# chuveiro.net
KiCad netlist of a schematic drawn in EAGLE
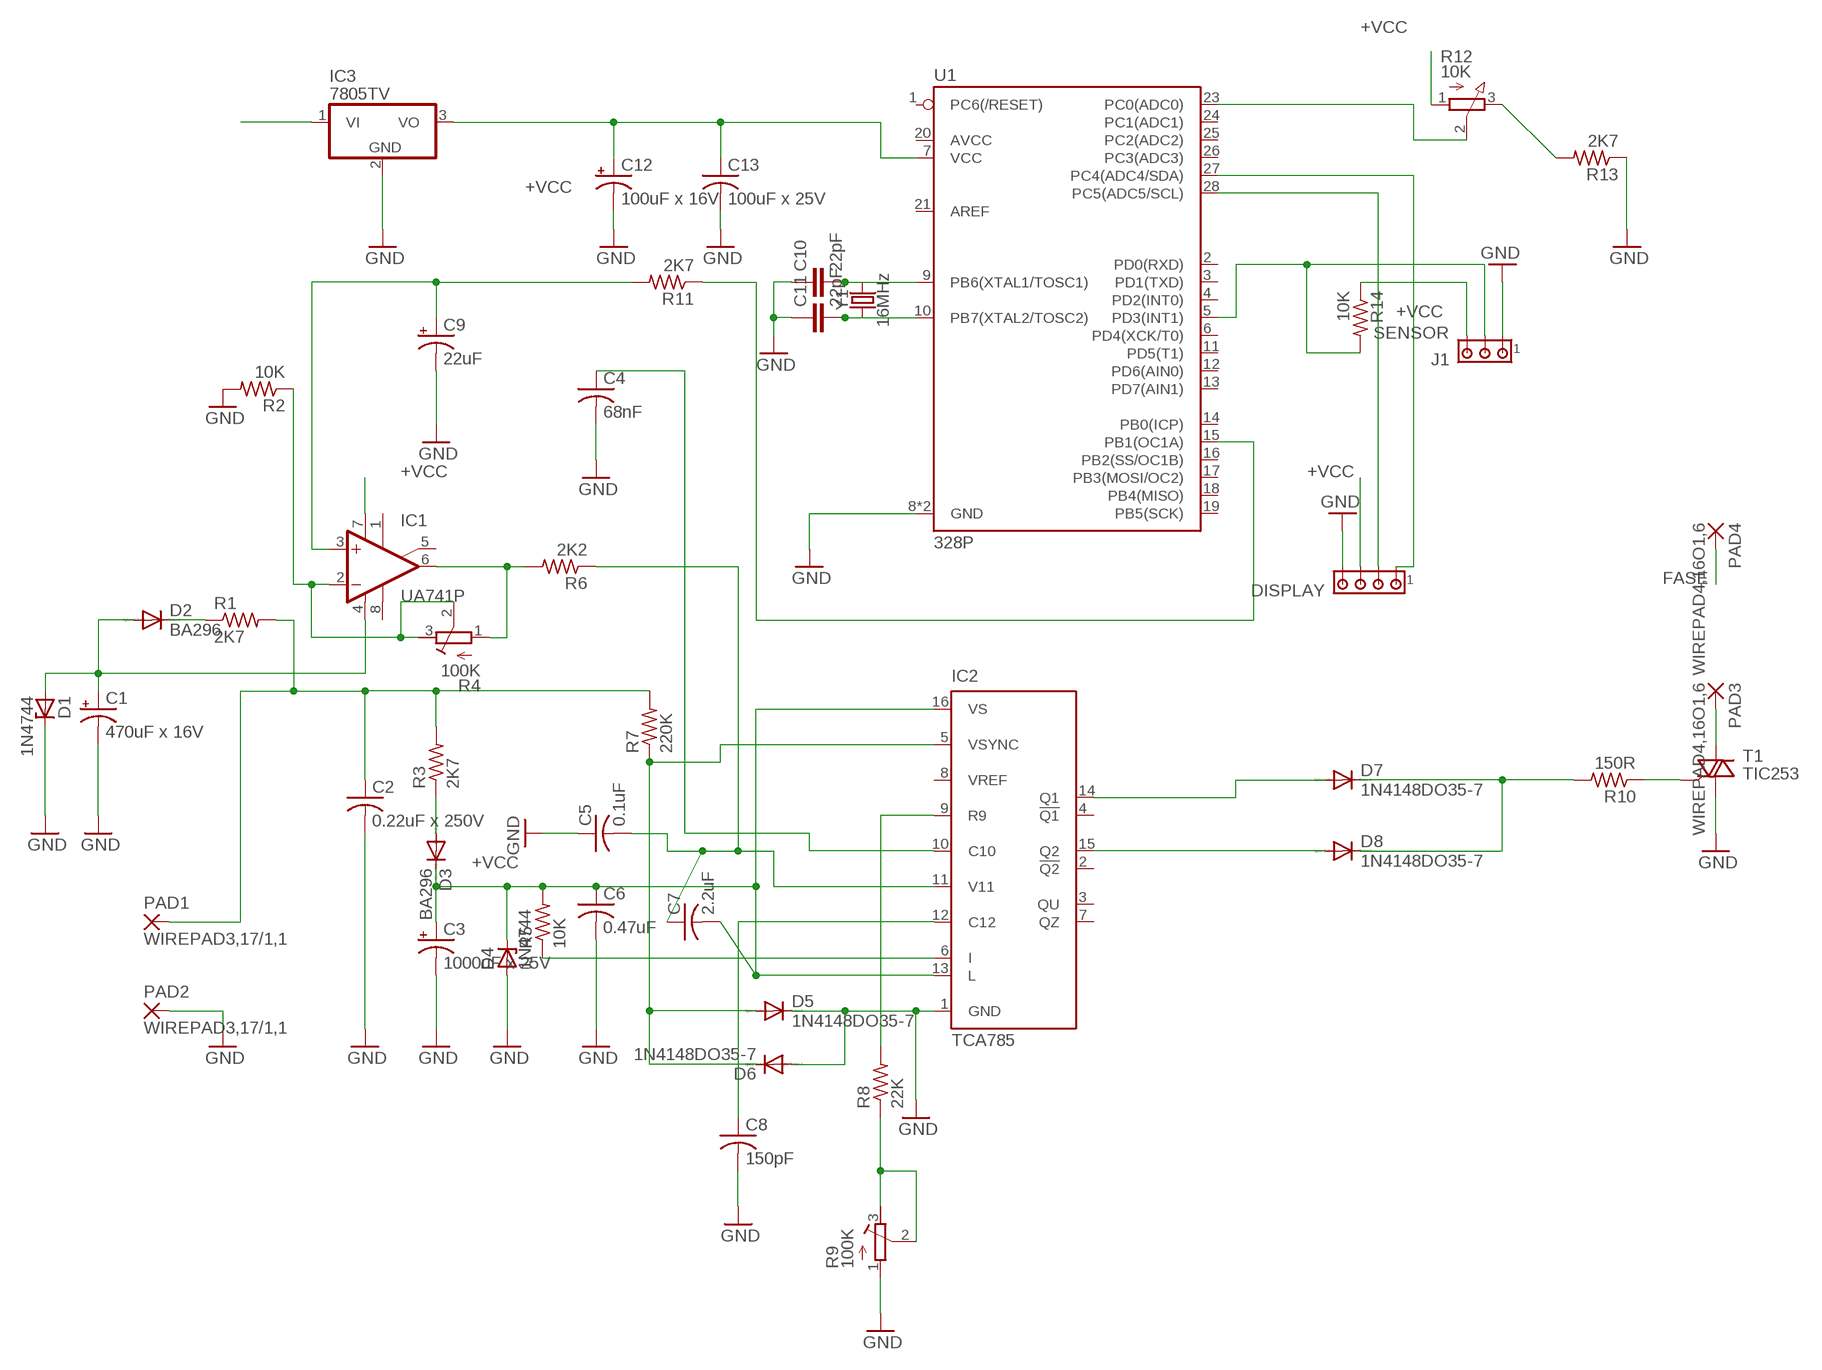
[diagram p0: schematic, sheet 1]

(export (version "E")
  (design (tool "Eeschema 10.0.6"))
  (components
    (comp (ref "C1")
      (value "470uF x 16V")
      (footprint "eagle-import:E5-6")
      (libsource (lib "eagle-import") (part "CPOL-USE5-6"))
    )
    (comp (ref "C2")
      (value "0.22uF x 250V")
      (footprint "eagle-import:C225-062X268")
      (libsource (lib "eagle-import") (part "C-US225-062X268"))
    )
    (comp (ref "C3")
      (value "1000uF x 25V")
      (footprint "eagle-import:E5-6")
      (libsource (lib "eagle-import") (part "CPOL-USE5-6"))
    )
    (comp (ref "C4")
      (value "68nF")
      (footprint "eagle-import:C025-050X050")
      (libsource (lib "eagle-import") (part "C-US025-050X050"))
    )
    (comp (ref "C5")
      (value "0.1uF")
      (footprint "eagle-import:C025-050X050")
      (libsource (lib "eagle-import") (part "C-US025-050X050"))
    )
    (comp (ref "C6")
      (value "0.47uF")
      (footprint "eagle-import:C025-050X050")
      (libsource (lib "eagle-import") (part "C-US025-050X050"))
    )
    (comp (ref "C7")
      (value "2.2uF")
      (footprint "eagle-import:C025-050X050")
      (libsource (lib "eagle-import") (part "C-US025-050X050"))
    )
    (comp (ref "C8")
      (value "150pF")
      (footprint "eagle-import:C025-050X050")
      (libsource (lib "eagle-import") (part "C-US025-050X050"))
    )
    (comp (ref "C9")
      (value "22uF")
      (footprint "eagle-import:E5-6")
      (libsource (lib "eagle-import") (part "CPOL-USE5-6"))
    )
    (comp (ref "C10")
      (value "22pF")
      (footprint "eagle-import:C025-024X044")
      (libsource (lib "eagle-import") (part "C-EU025-024X044"))
    )
    (comp (ref "C11")
      (value "22pF")
      (footprint "eagle-import:C025-024X044")
      (libsource (lib "eagle-import") (part "C-EU025-024X044"))
    )
    (comp (ref "C12")
      (value "100uF x 16V")
      (footprint "eagle-import:E5-6")
      (libsource (lib "eagle-import") (part "CPOL-USE5-6"))
    )
    (comp (ref "C13")
      (value "100uF x 25V")
      (footprint "eagle-import:C225-062X268")
      (libsource (lib "eagle-import") (part "C-US225-062X268"))
    )
    (comp (ref "D1")
      (value "1N4744")
      (footprint "eagle-import:DO41Z10")
      (libsource (lib "eagle-import") (part "ZENER-DIODEDO41Z10"))
    )
    (comp (ref "D2")
      (value "BA296")
      (footprint "eagle-import:P2-15")
      (libsource (lib "eagle-import") (part "BA296"))
    )
    (comp (ref "D3")
      (value "BA296")
      (footprint "eagle-import:P2-15")
      (libsource (lib "eagle-import") (part "BA296"))
    )
    (comp (ref "D4")
      (value "1N4744")
      (footprint "eagle-import:DO41Z10")
      (libsource (lib "eagle-import") (part "ZENER-DIODEDO41Z10"))
    )
    (comp (ref "D5")
      (value "1N4148DO35-7")
      (footprint "eagle-import:DO35-7")
      (libsource (lib "eagle-import") (part "1N4148DO35-7"))
    )
    (comp (ref "D6")
      (value "1N4148DO35-7")
      (footprint "eagle-import:DO35-7")
      (libsource (lib "eagle-import") (part "1N4148DO35-7"))
    )
    (comp (ref "D7")
      (value "1N4148DO35-7")
      (footprint "eagle-import:DO35-7")
      (libsource (lib "eagle-import") (part "1N4148DO35-7"))
    )
    (comp (ref "D8")
      (value "1N4148DO35-7")
      (footprint "eagle-import:DO35-7")
      (libsource (lib "eagle-import") (part "1N4148DO35-7"))
    )
    (comp (ref "DISPLAY")
      (value "MTA04-100")
      (footprint "eagle-import:10X04MTA")
      (libsource (lib "eagle-import") (part "MTA04-100"))
    )
    (comp (ref "IC1")
      (value "UA741P")
      (footprint "eagle-import:DIL08")
      (libsource (lib "eagle-import") (part "741PUA"))
    )
    (comp (ref "IC2")
      (value "TCA785")
      (footprint "eagle-import:DIL16")
      (libsource (lib "eagle-import") (part "TCA785"))
    )
    (comp (ref "IC3")
      (value "7805TV")
      (footprint "eagle-import:TO220V")
      (libsource (lib "eagle-import") (part "78TV05"))
    )
    (comp (ref "J1")
      (value "SENSOR")
      (footprint "eagle-import:10X03MTA")
      (libsource (lib "eagle-import") (part "MTA03-100"))
    )
    (comp (ref "PAD1")
      (value "WIREPAD3,17/1,1")
      (footprint "eagle-import:3,17_1,1")
      (libsource (lib "eagle-import") (part "WIREPAD3,17/1,1"))
    )
    (comp (ref "PAD2")
      (value "WIREPAD3,17/1,1")
      (footprint "eagle-import:3,17_1,1")
      (libsource (lib "eagle-import") (part "WIREPAD3,17/1,1"))
    )
    (comp (ref "PAD3")
      (value "WIREPAD4,16O1,6")
      (footprint "eagle-import:4,16O1,6")
      (libsource (lib "eagle-import") (part "WIREPAD4,16O1,6"))
    )
    (comp (ref "PAD4")
      (value "WIREPAD4,16O1,6")
      (footprint "eagle-import:4,16O1,6")
      (libsource (lib "eagle-import") (part "WIREPAD4,16O1,6"))
    )
    (comp (ref "R1")
      (value "2K7")
      (footprint "eagle-import:0207_10")
      (libsource (lib "eagle-import") (part "R-US_0207/10"))
    )
    (comp (ref "R2")
      (value "10K")
      (footprint "eagle-import:0207_10")
      (libsource (lib "eagle-import") (part "R-US_0207/10"))
    )
    (comp (ref "R3")
      (value "2K7")
      (footprint "eagle-import:0207_10")
      (libsource (lib "eagle-import") (part "R-US_0207/10"))
    )
    (comp (ref "R4")
      (value "100K")
      (footprint "eagle-import:RTRIM64Y")
      (libsource (lib "eagle-import") (part "R-TRIMM64Y"))
    )
    (comp (ref "R5")
      (value "10K")
      (footprint "eagle-import:0207_10")
      (libsource (lib "eagle-import") (part "R-US_0207/10"))
    )
    (comp (ref "R6")
      (value "2K2")
      (footprint "eagle-import:0207_10")
      (libsource (lib "eagle-import") (part "R-US_0207/10"))
    )
    (comp (ref "R7")
      (value "220K")
      (footprint "eagle-import:0207_10")
      (libsource (lib "eagle-import") (part "R-US_0207/10"))
    )
    (comp (ref "R8")
      (value "22K")
      (footprint "eagle-import:0207_10")
      (libsource (lib "eagle-import") (part "R-US_0207/10"))
    )
    (comp (ref "R9")
      (value "100K")
      (footprint "eagle-import:RTRIM64Y")
      (libsource (lib "eagle-import") (part "R-TRIMM64Y"))
    )
    (comp (ref "R10")
      (value "150R")
      (footprint "eagle-import:0207_10")
      (libsource (lib "eagle-import") (part "resistor_R-US_0207/10"))
    )
    (comp (ref "R11")
      (value "2K7")
      (footprint "eagle-import:0207_10")
      (libsource (lib "eagle-import") (part "R-US_0207/10"))
    )
    (comp (ref "R12")
      (value "10K")
      (footprint "eagle-import:3RP_1610N")
      (libsource (lib "eagle-import") (part "3RP/1610N"))
    )
    (comp (ref "R13")
      (value "2K7")
      (footprint "eagle-import:0207_10")
      (libsource (lib "eagle-import") (part "R-US_0207/10"))
    )
    (comp (ref "R14")
      (value "10K")
      (footprint "eagle-import:0207_10")
      (libsource (lib "eagle-import") (part "R-US_0207/10"))
    )
    (comp (ref "T1")
      (value "TIC253")
      (footprint "eagle-import:TO218DS")
      (libsource (lib "eagle-import") (part "TIC253"))
    )
    (comp (ref "U1")
      (value "328P")
      (footprint "eagle-import:DIP28")
      (libsource (lib "eagle-import") (part "ATMEGA328P_PDIP"))
    )
    (comp (ref "Y1")
      (value "16MHz")
      (footprint "eagle-import:HC49US")
      (libsource (lib "eagle-import") (part "CRYSTAL-16MHZPTH-HC49US"))
    )
  )
  (nets
    (net (code "1") (name "/+VCC") (class "Default")
      (node (ref "C3") (pin "+") (pinfunction "+_+") (pintype "passive"))
      (node (ref "C6") (pin "1") (pinfunction "1_1") (pintype "passive"))
      (node (ref "C7") (pin "2") (pinfunction "2_2") (pintype "passive"))
      (node (ref "D3") (pin "C") (pinfunction "C_C") (pintype "passive"))
      (node (ref "D4") (pin "C") (pinfunction "C_C") (pintype "passive"))
      (node (ref "DISPLAY") (pin "3") (pinfunction "3_3") (pintype "passive"))
      (node (ref "IC1") (pin "7") (pinfunction "V+_7") (pintype "power_in"))
      (node (ref "IC2") (pin "13") (pinfunction "L_13") (pintype "input"))
      (node (ref "IC2") (pin "16") (pinfunction "VS_16") (pintype "input"))
      (node (ref "IC3") (pin "1") (pinfunction "VI_1") (pintype "input"))
      (node (ref "J1") (pin "3") (pinfunction "3_3") (pintype "passive"))
      (node (ref "R12") (pin "1") (pinfunction "A_1") (pintype "passive"))
      (node (ref "R14") (pin "1") (pinfunction "1_1") (pintype "passive"))
      (node (ref "R5") (pin "2") (pinfunction "2_2") (pintype "passive"))
    )
    (net (code "2") (name "/FASE") (class "Default")
      (node (ref "C2") (pin "1") (pinfunction "1_1") (pintype "passive"))
      (node (ref "PAD1") (pin "1") (pinfunction "P_1") (pintype "passive"))
      (node (ref "PAD4") (pin "1") (pinfunction "P_1") (pintype "passive"))
      (node (ref "R1") (pin "2") (pinfunction "2_2") (pintype "passive"))
      (node (ref "R3") (pin "2") (pinfunction "2_2") (pintype "passive"))
      (node (ref "R7") (pin "2") (pinfunction "2_2") (pintype "passive"))
    )
    (net (code "3") (name "GND") (class "Default")
      (node (ref "C1") (pin "-") (pinfunction "-_-") (pintype "passive"))
      (node (ref "C10") (pin "1") (pinfunction "1_1") (pintype "passive"))
      (node (ref "C11") (pin "1") (pinfunction "1_1") (pintype "passive"))
      (node (ref "C12") (pin "-") (pinfunction "-_-") (pintype "passive"))
      (node (ref "C13") (pin "2") (pinfunction "2_2") (pintype "passive"))
      (node (ref "C2") (pin "2") (pinfunction "2_2") (pintype "passive"))
      (node (ref "C3") (pin "-") (pinfunction "-_-") (pintype "passive"))
      (node (ref "C4") (pin "2") (pinfunction "2_2") (pintype "passive"))
      (node (ref "C5") (pin "1") (pinfunction "1_1") (pintype "passive"))
      (node (ref "C6") (pin "2") (pinfunction "2_2") (pintype "passive"))
      (node (ref "C8") (pin "2") (pinfunction "2_2") (pintype "passive"))
      (node (ref "C9") (pin "-") (pinfunction "-_-") (pintype "passive"))
      (node (ref "D1") (pin "C") (pinfunction "C_C") (pintype "passive"))
      (node (ref "D4") (pin "A") (pinfunction "A_A") (pintype "passive"))
      (node (ref "D5") (pin "C") (pinfunction "C_C") (pintype "passive"))
      (node (ref "D6") (pin "A") (pinfunction "A_A") (pintype "passive"))
      (node (ref "DISPLAY") (pin "4") (pinfunction "4_4") (pintype "passive"))
      (node (ref "IC2") (pin "1") (pinfunction "GND_1") (pintype "power_in"))
      (node (ref "IC3") (pin "2") (pinfunction "GND_2") (pintype "passive"))
      (node (ref "J1") (pin "1") (pinfunction "1_1") (pintype "passive"))
      (node (ref "PAD2") (pin "1") (pinfunction "P_1") (pintype "passive"))
      (node (ref "R13") (pin "1") (pinfunction "1_1") (pintype "passive"))
      (node (ref "R2") (pin "2") (pinfunction "2_2") (pintype "passive"))
      (node (ref "R9") (pin "1") (pinfunction "A_1") (pintype "passive"))
      (node (ref "T1") (pin "A1") (pinfunction "A1_A1") (pintype "passive"))
      (node (ref "U1") (pin "22") (pinfunction "GND_22") (pintype "bidirectional"))
      (node (ref "U1") (pin "8") (pinfunction "GND_8") (pintype "bidirectional"))
    )
    (net (code "4") (name "Net-(D2-PadC)") (class "Default")
      (node (ref "D2") (pin "C") (pinfunction "C_C") (pintype "passive"))
      (node (ref "R1") (pin "1") (pinfunction "1_1") (pintype "passive"))
    )
    (net (code "5") (name "Net-(D3-PadA)") (class "Default")
      (node (ref "D3") (pin "A") (pinfunction "A_A") (pintype "passive"))
      (node (ref "R3") (pin "1") (pinfunction "1_1") (pintype "passive"))
    )
    (net (code "6") (name "Net-(D7-PadC)") (class "Default")
      (node (ref "D7") (pin "C") (pinfunction "C_C") (pintype "passive"))
      (node (ref "D8") (pin "C") (pinfunction "C_C") (pintype "passive"))
      (node (ref "R10") (pin "2") (pinfunction "2_2") (pintype "passive"))
    )
    (net (code "7") (name "Net-(IC1-+IN)") (class "Default")
      (node (ref "C9") (pin "+") (pinfunction "+_+") (pintype "passive"))
      (node (ref "IC1") (pin "3") (pinfunction "+IN_3") (pintype "input"))
      (node (ref "R11") (pin "2") (pinfunction "2_2") (pintype "passive"))
    )
    (net (code "8") (name "Net-(IC1--IN)") (class "Default")
      (node (ref "IC1") (pin "2") (pinfunction "-IN_2") (pintype "input"))
      (node (ref "R2") (pin "1") (pinfunction "1_1") (pintype "passive"))
      (node (ref "R4") (pin "2") (pinfunction "S_2") (pintype "passive"))
      (node (ref "R4") (pin "3") (pinfunction "E_3") (pintype "passive"))
    )
    (net (code "9") (name "Net-(IC1-OUT)") (class "Default")
      (node (ref "IC1") (pin "6") (pinfunction "OUT_6") (pintype "output"))
      (node (ref "R4") (pin "1") (pinfunction "A_1") (pintype "passive"))
      (node (ref "R6") (pin "2") (pinfunction "2_2") (pintype "passive"))
    )
    (net (code "10") (name "Net-(IC1-V-)") (class "Default")
      (node (ref "C1") (pin "+") (pinfunction "+_+") (pintype "passive"))
      (node (ref "D1") (pin "A") (pinfunction "A_A") (pintype "passive"))
      (node (ref "D2") (pin "A") (pinfunction "A_A") (pintype "passive"))
      (node (ref "IC1") (pin "4") (pinfunction "V-_4") (pintype "power_in"))
    )
    (net (code "11") (name "Net-(IC2-C10)") (class "Default")
      (node (ref "C4") (pin "1") (pinfunction "1_1") (pintype "passive"))
      (node (ref "IC2") (pin "10") (pinfunction "C10_10") (pintype "input"))
    )
    (net (code "12") (name "Net-(IC2-C12)") (class "Default")
      (node (ref "C8") (pin "1") (pinfunction "1_1") (pintype "passive"))
      (node (ref "IC2") (pin "12") (pinfunction "C12_12") (pintype "input"))
    )
    (net (code "13") (name "Net-(IC2-I)") (class "Default")
      (node (ref "IC2") (pin "6") (pinfunction "I_6") (pintype "input"))
      (node (ref "R5") (pin "1") (pinfunction "1_1") (pintype "passive"))
    )
    (net (code "14") (name "Net-(IC2-Q1)") (class "Default")
      (node (ref "D7") (pin "A") (pinfunction "A_A") (pintype "passive"))
      (node (ref "IC2") (pin "14") (pinfunction "Q1_14") (pintype "output"))
    )
    (net (code "15") (name "Net-(IC2-Q2)") (class "Default")
      (node (ref "D8") (pin "A") (pinfunction "A_A") (pintype "passive"))
      (node (ref "IC2") (pin "15") (pinfunction "Q2_15") (pintype "output"))
    )
    (net (code "16") (name "Net-(IC2-R9)") (class "Default")
      (node (ref "IC2") (pin "9") (pinfunction "R9_9") (pintype "input"))
      (node (ref "R8") (pin "2") (pinfunction "2_2") (pintype "passive"))
    )
    (net (code "17") (name "Net-(IC2-V11)") (class "Default")
      (node (ref "C5") (pin "2") (pinfunction "2_2") (pintype "passive"))
      (node (ref "C7") (pin "1") (pinfunction "1_1") (pintype "passive"))
      (node (ref "IC2") (pin "11") (pinfunction "V11_11") (pintype "input"))
      (node (ref "R6") (pin "1") (pinfunction "1_1") (pintype "passive"))
    )
    (net (code "18") (name "Net-(IC2-VSYNC)") (class "Default")
      (node (ref "D5") (pin "A") (pinfunction "A_A") (pintype "passive"))
      (node (ref "D6") (pin "C") (pinfunction "C_C") (pintype "passive"))
      (node (ref "IC2") (pin "5") (pinfunction "VSYNC_5") (pintype "input"))
      (node (ref "R7") (pin "1") (pinfunction "1_1") (pintype "passive"))
    )
    (net (code "19") (name "Net-(IC3-VO)") (class "Default")
      (node (ref "C12") (pin "+") (pinfunction "+_+") (pintype "passive"))
      (node (ref "C13") (pin "1") (pinfunction "1_1") (pintype "passive"))
      (node (ref "IC3") (pin "3") (pinfunction "VO_3") (pintype "passive"))
      (node (ref "U1") (pin "7") (pinfunction "VCC_7") (pintype "bidirectional"))
    )
    (net (code "20") (name "Net-(PAD3-P)") (class "Default")
      (node (ref "PAD3") (pin "1") (pinfunction "P_1") (pintype "passive"))
      (node (ref "T1") (pin "A2") (pinfunction "A2_A2") (pintype "passive"))
    )
    (net (code "21") (name "Net-(R9-E)") (class "Default")
      (node (ref "R8") (pin "1") (pinfunction "1_1") (pintype "passive"))
      (node (ref "R9") (pin "2") (pinfunction "S_2") (pintype "passive"))
      (node (ref "R9") (pin "3") (pinfunction "E_3") (pintype "passive"))
    )
    (net (code "22") (name "Net-(R10-Pad1)") (class "Default")
      (node (ref "R10") (pin "1") (pinfunction "1_1") (pintype "passive"))
      (node (ref "T1") (pin "G") (pinfunction "G_G") (pintype "passive"))
    )
    (net (code "23") (name "Net-(R12-E)") (class "Default")
      (node (ref "R12") (pin "3") (pinfunction "E_3") (pintype "passive"))
      (node (ref "R13") (pin "2") (pinfunction "2_2") (pintype "passive"))
    )
    (net (code "24") (name "Net-(R12-S)") (class "Default")
      (node (ref "R12") (pin "2") (pinfunction "S_2") (pintype "passive"))
      (node (ref "U1") (pin "23") (pinfunction "PC0(ADC0)_23") (pintype "bidirectional"))
    )
    (net (code "25") (name "Net-(U1-PB1(OC1A))") (class "Default")
      (node (ref "R11") (pin "1") (pinfunction "1_1") (pintype "passive"))
      (node (ref "U1") (pin "15") (pinfunction "PB1(OC1A)_15") (pintype "bidirectional"))
    )
    (net (code "26") (name "Net-(U1-PB6(XTAL1{slash}TOSC1))") (class "Default")
      (node (ref "C10") (pin "2") (pinfunction "2_2") (pintype "passive"))
      (node (ref "U1") (pin "9") (pinfunction "PB6(XTAL1/TOSC1)_9") (pintype "bidirectional"))
      (node (ref "Y1") (pin "2") (pinfunction "2_2") (pintype "passive"))
    )
    (net (code "27") (name "Net-(U1-PB7(XTAL2{slash}TOSC2))") (class "Default")
      (node (ref "C11") (pin "2") (pinfunction "2_2") (pintype "passive"))
      (node (ref "U1") (pin "10") (pinfunction "PB7(XTAL2/TOSC2)_10") (pintype "bidirectional"))
      (node (ref "Y1") (pin "1") (pinfunction "1_1") (pintype "passive"))
    )
    (net (code "28") (name "Net-(U1-PC4(ADC4{slash}SDA))") (class "Default")
      (node (ref "DISPLAY") (pin "1") (pinfunction "1_1") (pintype "passive"))
      (node (ref "U1") (pin "27") (pinfunction "PC4(ADC4/SDA)_27") (pintype "bidirectional"))
    )
    (net (code "29") (name "Net-(U1-PC5(ADC5{slash}SCL))") (class "Default")
      (node (ref "DISPLAY") (pin "2") (pinfunction "2_2") (pintype "passive"))
      (node (ref "U1") (pin "28") (pinfunction "PC5(ADC5/SCL)_28") (pintype "bidirectional"))
    )
    (net (code "30") (name "Net-(U1-PD3(INT1))") (class "Default")
      (node (ref "J1") (pin "2") (pinfunction "2_2") (pintype "passive"))
      (node (ref "R14") (pin "2") (pinfunction "2_2") (pintype "passive"))
      (node (ref "U1") (pin "5") (pinfunction "PD3(INT1)_5") (pintype "bidirectional"))
    )
    (net (code "31") (name "unconnected-(IC1-ON1-Pad1)") (class "Default")
      (node (ref "IC1") (pin "1") (pinfunction "ON1_1") (pintype "passive"))
    )
    (net (code "32") (name "unconnected-(IC1-ON2-Pad5)") (class "Default")
      (node (ref "IC1") (pin "5") (pinfunction "ON2_5") (pintype "passive"))
    )
    (net (code "33") (name "unconnected-(IC1-OPT-Pad8)") (class "Default")
      (node (ref "IC1") (pin "8") (pinfunction "OPT_8") (pintype "passive"))
    )
    (net (code "34") (name "unconnected-(IC2-QU-Pad3)") (class "Default")
      (node (ref "IC2") (pin "3") (pinfunction "QU_3") (pintype "output"))
    )
    (net (code "35") (name "unconnected-(IC2-QZ-Pad7)") (class "Default")
      (node (ref "IC2") (pin "7") (pinfunction "QZ_7") (pintype "output"))
    )
    (net (code "36") (name "unconnected-(IC2-VREF-Pad8)") (class "Default")
      (node (ref "IC2") (pin "8") (pinfunction "VREF_8") (pintype "input"))
    )
    (net (code "37") (name "unconnected-(IC2-~{Q1}-Pad4)") (class "Default")
      (node (ref "IC2") (pin "4") (pinfunction "~{Q1}_4") (pintype "output"))
    )
    (net (code "38") (name "unconnected-(IC2-~{Q2}-Pad2)") (class "Default")
      (node (ref "IC2") (pin "2") (pinfunction "~{Q2}_2") (pintype "output"))
    )
    (net (code "39") (name "unconnected-(U1-AREF-Pad21)") (class "Default")
      (node (ref "U1") (pin "21") (pinfunction "AREF_21") (pintype "bidirectional"))
    )
    (net (code "40") (name "unconnected-(U1-AVCC-Pad20)") (class "Default")
      (node (ref "U1") (pin "20") (pinfunction "AVCC_20") (pintype "bidirectional"))
    )
    (net (code "41") (name "unconnected-(U1-PB0(ICP)-Pad14)") (class "Default")
      (node (ref "U1") (pin "14") (pinfunction "PB0(ICP)_14") (pintype "bidirectional"))
    )
    (net (code "42") (name "unconnected-(U1-PB2(SS{slash}OC1B)-Pad16)") (class "Default")
      (node (ref "U1") (pin "16") (pinfunction "PB2(SS/OC1B)_16") (pintype "bidirectional"))
    )
    (net (code "43") (name "unconnected-(U1-PB3(MOSI{slash}OC2)-Pad17)") (class "Default")
      (node (ref "U1") (pin "17") (pinfunction "PB3(MOSI/OC2)_17") (pintype "bidirectional"))
    )
    (net (code "44") (name "unconnected-(U1-PB4(MISO)-Pad18)") (class "Default")
      (node (ref "U1") (pin "18") (pinfunction "PB4(MISO)_18") (pintype "bidirectional"))
    )
    (net (code "45") (name "unconnected-(U1-PB5(SCK)-Pad19)") (class "Default")
      (node (ref "U1") (pin "19") (pinfunction "PB5(SCK)_19") (pintype "bidirectional"))
    )
    (net (code "46") (name "unconnected-(U1-PC1(ADC1)-Pad24)") (class "Default")
      (node (ref "U1") (pin "24") (pinfunction "PC1(ADC1)_24") (pintype "bidirectional"))
    )
    (net (code "47") (name "unconnected-(U1-PC2(ADC2)-Pad25)") (class "Default")
      (node (ref "U1") (pin "25") (pinfunction "PC2(ADC2)_25") (pintype "bidirectional"))
    )
    (net (code "48") (name "unconnected-(U1-PC3(ADC3)-Pad26)") (class "Default")
      (node (ref "U1") (pin "26") (pinfunction "PC3(ADC3)_26") (pintype "bidirectional"))
    )
    (net (code "49") (name "unconnected-(U1-PC6({slash}RESET)-Pad1)") (class "Default")
      (node (ref "U1") (pin "1") (pinfunction "PC6(/RESET)_1") (pintype "bidirectional"))
    )
    (net (code "50") (name "unconnected-(U1-PD0(RXD)-Pad2)") (class "Default")
      (node (ref "U1") (pin "2") (pinfunction "PD0(RXD)_2") (pintype "bidirectional"))
    )
    (net (code "51") (name "unconnected-(U1-PD1(TXD)-Pad3)") (class "Default")
      (node (ref "U1") (pin "3") (pinfunction "PD1(TXD)_3") (pintype "bidirectional"))
    )
    (net (code "52") (name "unconnected-(U1-PD2(INT0)-Pad4)") (class "Default")
      (node (ref "U1") (pin "4") (pinfunction "PD2(INT0)_4") (pintype "bidirectional"))
    )
    (net (code "53") (name "unconnected-(U1-PD4(XCK{slash}T0)-Pad6)") (class "Default")
      (node (ref "U1") (pin "6") (pinfunction "PD4(XCK/T0)_6") (pintype "bidirectional"))
    )
    (net (code "54") (name "unconnected-(U1-PD5(T1)-Pad11)") (class "Default")
      (node (ref "U1") (pin "11") (pinfunction "PD5(T1)_11") (pintype "bidirectional"))
    )
    (net (code "55") (name "unconnected-(U1-PD6(AIN0)-Pad12)") (class "Default")
      (node (ref "U1") (pin "12") (pinfunction "PD6(AIN0)_12") (pintype "bidirectional"))
    )
    (net (code "56") (name "unconnected-(U1-PD7(AIN1)-Pad13)") (class "Default")
      (node (ref "U1") (pin "13") (pinfunction "PD7(AIN1)_13") (pintype "bidirectional"))
    )
  )
)
